# LdcPower.net
KiCad netlist of a schematic drawn in Altium Designer
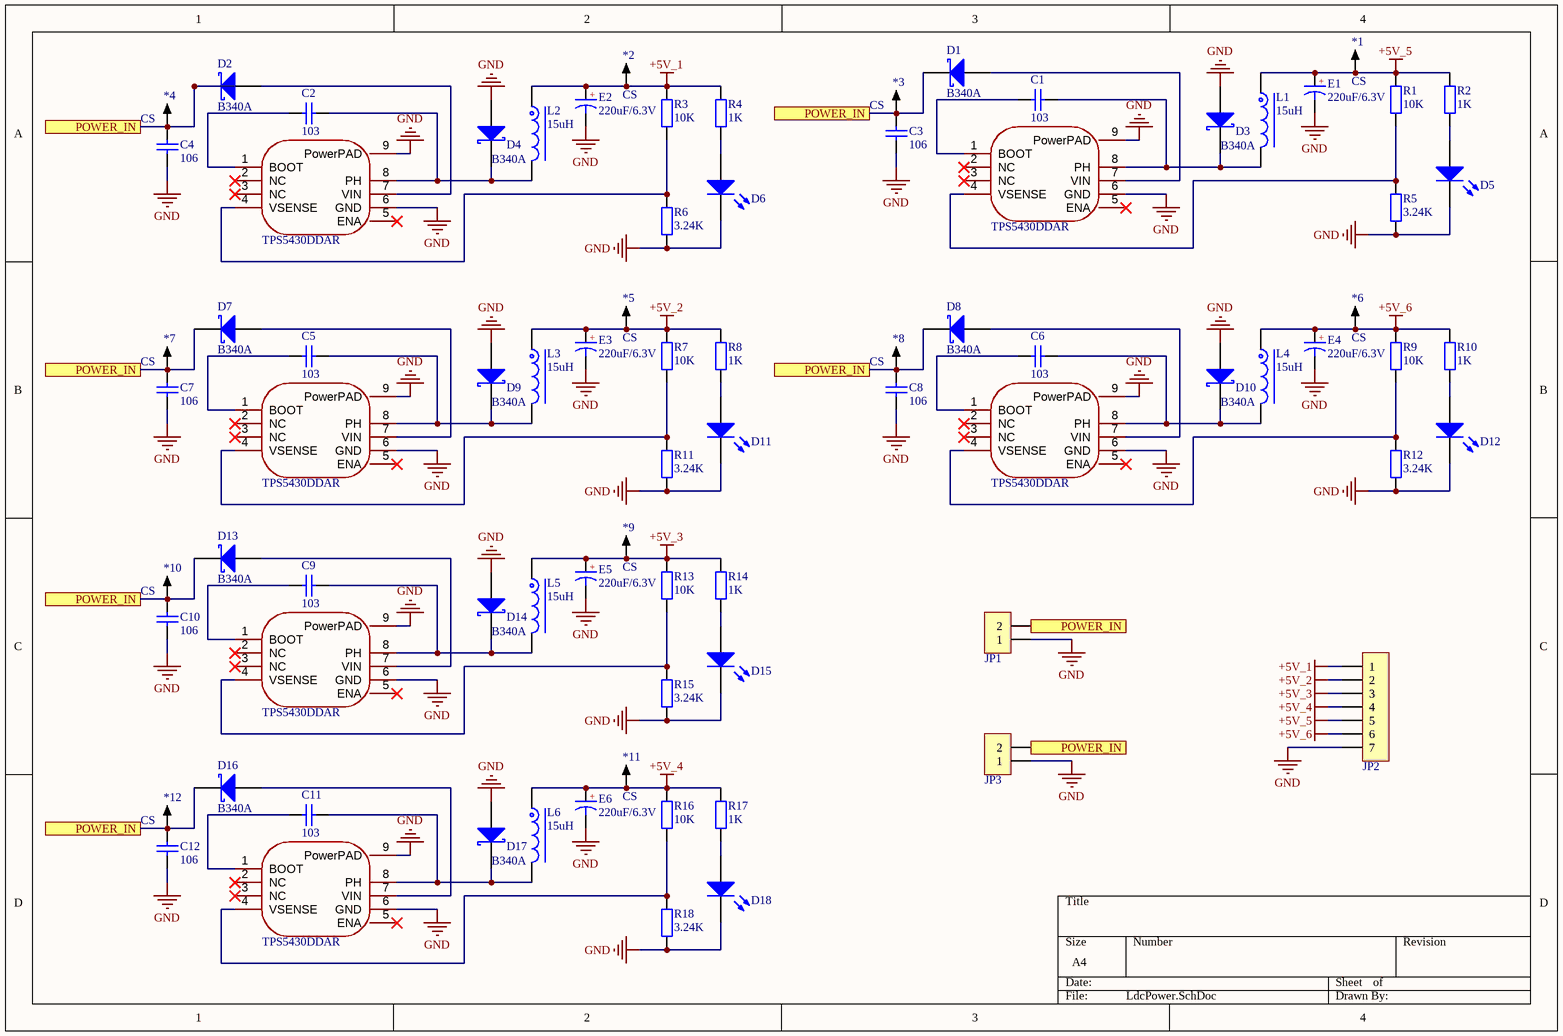
[diagram p0: LdcPower.SchDoc]

(export (version "E")
  (design (tool "Eeschema 10.0.6"))
  (components
    (comp (ref "*1")
      (value "CS")
      (footprint "TEST 1.2")
      (description "探针焊盘")
      (libsource (lib "Wlink") (part "CS"))
    )
    (comp (ref "*2")
      (value "CS")
      (footprint "TEST 1.2")
      (description "探针焊盘")
      (libsource (lib "Wlink") (part "CS"))
    )
    (comp (ref "*3")
      (value "CS")
      (footprint "TEST 1.2")
      (description "探针焊盘")
      (libsource (lib "Wlink") (part "CS"))
    )
    (comp (ref "*4")
      (value "CS")
      (footprint "TEST 1.2")
      (description "探针焊盘")
      (libsource (lib "Wlink") (part "CS"))
    )
    (comp (ref "*5")
      (value "CS")
      (footprint "TEST 1.2")
      (description "探针焊盘")
      (libsource (lib "Wlink") (part "CS"))
    )
    (comp (ref "*6")
      (value "CS")
      (footprint "TEST 1.2")
      (description "探针焊盘")
      (libsource (lib "Wlink") (part "CS"))
    )
    (comp (ref "*7")
      (value "CS")
      (footprint "TEST 1.2")
      (description "探针焊盘")
      (libsource (lib "Wlink") (part "CS"))
    )
    (comp (ref "*8")
      (value "CS")
      (footprint "TEST 1.2")
      (description "探针焊盘")
      (libsource (lib "Wlink") (part "CS"))
    )
    (comp (ref "*9")
      (value "CS")
      (footprint "TEST 1.2")
      (description "探针焊盘")
      (libsource (lib "Wlink") (part "CS"))
    )
    (comp (ref "*10")
      (value "CS")
      (footprint "TEST 1.2")
      (description "探针焊盘")
      (libsource (lib "Wlink") (part "CS"))
    )
    (comp (ref "*11")
      (value "CS")
      (footprint "TEST 1.2")
      (description "探针焊盘")
      (libsource (lib "Wlink") (part "CS"))
    )
    (comp (ref "*12")
      (value "CS")
      (footprint "TEST 1.2")
      (description "探针焊盘")
      (libsource (lib "Wlink") (part "CS"))
    )
    (comp (ref "C1")
      (value "103")
      (footprint "C0603_L")
      (description "贴片电容/MLCC电容")
      (libsource (lib "Wlink") (part "C"))
    )
    (comp (ref "C2")
      (value "103")
      (footprint "C0603_L")
      (description "贴片电容/MLCC电容")
      (libsource (lib "Wlink") (part "C"))
    )
    (comp (ref "C3")
      (value "106")
      (footprint "C0603_L")
      (description "贴片电容/MLCC电容")
      (libsource (lib "Wlink") (part "C"))
    )
    (comp (ref "C4")
      (value "106")
      (footprint "C0603_L")
      (description "贴片电容/MLCC电容")
      (libsource (lib "Wlink") (part "C"))
    )
    (comp (ref "C5")
      (value "103")
      (footprint "C0603_L")
      (description "贴片电容/MLCC电容")
      (libsource (lib "Wlink") (part "C"))
    )
    (comp (ref "C6")
      (value "103")
      (footprint "C0603_L")
      (description "贴片电容/MLCC电容")
      (libsource (lib "Wlink") (part "C"))
    )
    (comp (ref "C7")
      (value "106")
      (footprint "C0603_L")
      (description "贴片电容/MLCC电容")
      (libsource (lib "Wlink") (part "C"))
    )
    (comp (ref "C8")
      (value "106")
      (footprint "C0603_L")
      (description "贴片电容/MLCC电容")
      (libsource (lib "Wlink") (part "C"))
    )
    (comp (ref "C9")
      (value "103")
      (footprint "C0603_L")
      (description "贴片电容/MLCC电容")
      (libsource (lib "Wlink") (part "C"))
    )
    (comp (ref "C10")
      (value "106")
      (footprint "C0603_L")
      (description "贴片电容/MLCC电容")
      (libsource (lib "Wlink") (part "C"))
    )
    (comp (ref "C11")
      (value "103")
      (footprint "C0603_L")
      (description "贴片电容/MLCC电容")
      (libsource (lib "Wlink") (part "C"))
    )
    (comp (ref "C12")
      (value "106")
      (footprint "C0603_L")
      (description "贴片电容/MLCC电容")
      (libsource (lib "Wlink") (part "C"))
    )
    (comp (ref "D1")
      (value "B340A")
      (footprint "SMA")
      (description "肖特基二极管")
      (libsource (lib "Wlink") (part "D-Schottky"))
    )
    (comp (ref "D2")
      (value "B340A")
      (footprint "SMA")
      (description "肖特基二极管")
      (libsource (lib "Wlink") (part "D-Schottky"))
    )
    (comp (ref "D3")
      (value "B340A")
      (footprint "SMA")
      (description "肖特基二极管")
      (libsource (lib "Wlink") (part "D-Schottky"))
    )
    (comp (ref "D4")
      (value "B340A")
      (footprint "SMA")
      (description "肖特基二极管")
      (libsource (lib "Wlink") (part "D-Schottky"))
    )
    (comp (ref "D5")
      (value "LED")
      (footprint "LED0603_R")
      (description "发光二极管")
      (fields (field (name "PUBLISHER") "Altium Limited"))
      (libsource (lib "fszhang") (part "LED0"))
    )
    (comp (ref "D6")
      (value "LED")
      (footprint "LED0603_R")
      (description "发光二极管")
      (fields (field (name "PUBLISHER") "Altium Limited"))
      (libsource (lib "fszhang") (part "LED0"))
    )
    (comp (ref "D7")
      (value "B340A")
      (footprint "SMA")
      (description "肖特基二极管")
      (libsource (lib "Wlink") (part "D-Schottky"))
    )
    (comp (ref "D8")
      (value "B340A")
      (footprint "SMA")
      (description "肖特基二极管")
      (libsource (lib "Wlink") (part "D-Schottky"))
    )
    (comp (ref "D9")
      (value "B340A")
      (footprint "SMA")
      (description "肖特基二极管")
      (libsource (lib "Wlink") (part "D-Schottky"))
    )
    (comp (ref "D10")
      (value "B340A")
      (footprint "SMA")
      (description "肖特基二极管")
      (libsource (lib "Wlink") (part "D-Schottky"))
    )
    (comp (ref "D11")
      (value "LED")
      (footprint "LED0603_R")
      (description "发光二极管")
      (fields (field (name "PUBLISHER") "Altium Limited"))
      (libsource (lib "fszhang") (part "LED0"))
    )
    (comp (ref "D12")
      (value "LED")
      (footprint "LED0603_R")
      (description "发光二极管")
      (fields (field (name "PUBLISHER") "Altium Limited"))
      (libsource (lib "fszhang") (part "LED0"))
    )
    (comp (ref "D13")
      (value "B340A")
      (footprint "SMA")
      (description "肖特基二极管")
      (libsource (lib "Wlink") (part "D-Schottky"))
    )
    (comp (ref "D14")
      (value "B340A")
      (footprint "SMA")
      (description "肖特基二极管")
      (libsource (lib "Wlink") (part "D-Schottky"))
    )
    (comp (ref "D15")
      (value "LED")
      (footprint "LED0603_R")
      (description "发光二极管")
      (fields (field (name "PUBLISHER") "Altium Limited"))
      (libsource (lib "fszhang") (part "LED0"))
    )
    (comp (ref "D16")
      (value "B340A")
      (footprint "SMA")
      (description "肖特基二极管")
      (libsource (lib "Wlink") (part "D-Schottky"))
    )
    (comp (ref "D17")
      (value "B340A")
      (footprint "SMA")
      (description "肖特基二极管")
      (libsource (lib "Wlink") (part "D-Schottky"))
    )
    (comp (ref "D18")
      (value "LED")
      (footprint "LED0603_R")
      (description "发光二极管")
      (fields (field (name "PUBLISHER") "Altium Limited"))
      (libsource (lib "fszhang") (part "LED0"))
    )
    (comp (ref "E1")
      (value "220uF/6.3V")
      (footprint "C_3528")
      (description "贴片钽电容")
      (libsource (lib "Wlink") (part "CT"))
    )
    (comp (ref "E2")
      (value "220uF/6.3V")
      (footprint "C_3528")
      (description "贴片钽电容")
      (libsource (lib "Wlink") (part "CT"))
    )
    (comp (ref "E3")
      (value "220uF/6.3V")
      (footprint "C_3528")
      (description "贴片钽电容")
      (libsource (lib "Wlink") (part "CT"))
    )
    (comp (ref "E4")
      (value "220uF/6.3V")
      (footprint "C_3528")
      (description "贴片钽电容")
      (libsource (lib "Wlink") (part "CT"))
    )
    (comp (ref "E5")
      (value "220uF/6.3V")
      (footprint "C_3528")
      (description "贴片钽电容")
      (libsource (lib "Wlink") (part "CT"))
    )
    (comp (ref "E6")
      (value "220uF/6.3V")
      (footprint "C_3528")
      (description "贴片钽电容")
      (libsource (lib "Wlink") (part "CT"))
    )
    (comp (ref "JP1")
      (value "HDR-1X2")
      (footprint "CONN-TH_XT60PW-M")
      (description "2P接插件")
      (libsource (lib "5.5 - 2.54mm连接器(KF2EDGK_XH2.54_2.54排针排母)") (part "Header 2"))
    )
    (comp (ref "JP2")
      (value "HDR-1X7")
      (footprint "CONN-SMD_7P-P2.54_MEGASTAR_ZX-XH2.54-7PWT")
      (description "7P接插件")
      (libsource (lib "MultiChannelLdc") (part "Header 7"))
    )
    (comp (ref "JP3")
      (value "HDR-1X2")
      (footprint "CONN-SMD_2P-P2.54_MEGASTAR_ZX-XH2.54-2PWT")
      (description "2P接插件")
      (libsource (lib "5.5 - 2.54mm连接器(KF2EDGK_XH2.54_2.54排针排母)") (part "Header 2"))
    )
    (comp (ref "L1")
      (value "15uH")
      (footprint "L-SMD-0630")
      (description "一体成型电感")
      (libsource (lib "Wlink") (part "L-Molding Choke"))
    )
    (comp (ref "L2")
      (value "15uH")
      (footprint "L-SMD-0630")
      (description "一体成型电感")
      (libsource (lib "Wlink") (part "L-Molding Choke"))
    )
    (comp (ref "L3")
      (value "15uH")
      (footprint "L-SMD-0630")
      (description "一体成型电感")
      (libsource (lib "Wlink") (part "L-Molding Choke"))
    )
    (comp (ref "L4")
      (value "15uH")
      (footprint "L-SMD-0630")
      (description "一体成型电感")
      (libsource (lib "Wlink") (part "L-Molding Choke"))
    )
    (comp (ref "L5")
      (value "15uH")
      (footprint "L-SMD-0630")
      (description "一体成型电感")
      (libsource (lib "Wlink") (part "L-Molding Choke"))
    )
    (comp (ref "L6")
      (value "15uH")
      (footprint "L-SMD-0630")
      (description "一体成型电感")
      (libsource (lib "Wlink") (part "L-Molding Choke"))
    )
    (comp (ref "R1")
      (value "10K")
      (footprint "R0603_L")
      (description "贴片电阻")
      (libsource (lib "Wlink") (part "R"))
    )
    (comp (ref "R2")
      (value "1K")
      (footprint "R0603_L")
      (description "贴片电阻")
      (libsource (lib "Wlink") (part "R"))
    )
    (comp (ref "R3")
      (value "10K")
      (footprint "R0603_L")
      (description "贴片电阻")
      (libsource (lib "Wlink") (part "R"))
    )
    (comp (ref "R4")
      (value "1K")
      (footprint "R0603_L")
      (description "贴片电阻")
      (libsource (lib "Wlink") (part "R"))
    )
    (comp (ref "R5")
      (value "3.24K")
      (footprint "R0603_L")
      (description "贴片电阻")
      (libsource (lib "Wlink") (part "R"))
    )
    (comp (ref "R6")
      (value "3.24K")
      (footprint "R0603_L")
      (description "贴片电阻")
      (libsource (lib "Wlink") (part "R"))
    )
    (comp (ref "R7")
      (value "10K")
      (footprint "R0603_L")
      (description "贴片电阻")
      (libsource (lib "Wlink") (part "R"))
    )
    (comp (ref "R8")
      (value "1K")
      (footprint "R0603_L")
      (description "贴片电阻")
      (libsource (lib "Wlink") (part "R"))
    )
    (comp (ref "R9")
      (value "10K")
      (footprint "R0603_L")
      (description "贴片电阻")
      (libsource (lib "Wlink") (part "R"))
    )
    (comp (ref "R10")
      (value "1K")
      (footprint "R0603_L")
      (description "贴片电阻")
      (libsource (lib "Wlink") (part "R"))
    )
    (comp (ref "R11")
      (value "3.24K")
      (footprint "R0603_L")
      (description "贴片电阻")
      (libsource (lib "Wlink") (part "R"))
    )
    (comp (ref "R12")
      (value "3.24K")
      (footprint "R0603_L")
      (description "贴片电阻")
      (libsource (lib "Wlink") (part "R"))
    )
    (comp (ref "R13")
      (value "10K")
      (footprint "R0603_L")
      (description "贴片电阻")
      (libsource (lib "Wlink") (part "R"))
    )
    (comp (ref "R14")
      (value "1K")
      (footprint "R0603_L")
      (description "贴片电阻")
      (libsource (lib "Wlink") (part "R"))
    )
    (comp (ref "R15")
      (value "3.24K")
      (footprint "R0603_L")
      (description "贴片电阻")
      (libsource (lib "Wlink") (part "R"))
    )
    (comp (ref "R16")
      (value "10K")
      (footprint "R0603_L")
      (description "贴片电阻")
      (libsource (lib "Wlink") (part "R"))
    )
    (comp (ref "R17")
      (value "1K")
      (footprint "R0603_L")
      (description "贴片电阻")
      (libsource (lib "Wlink") (part "R"))
    )
    (comp (ref "R18")
      (value "3.24K")
      (footprint "R0603_L")
      (description "贴片电阻")
      (libsource (lib "Wlink") (part "R"))
    )
    (comp (ref "U1")
      (value "TPS5430DDAR")
      (footprint "SOIC-8_EP")
      (libsource (lib "Wlink") (part "TPS5430DDAR"))
    )
    (comp (ref "U2")
      (value "TPS5430DDAR")
      (footprint "SOIC-8_EP")
      (libsource (lib "Wlink") (part "TPS5430DDAR"))
    )
    (comp (ref "U3")
      (value "TPS5430DDAR")
      (footprint "SOIC-8_EP")
      (libsource (lib "Wlink") (part "TPS5430DDAR"))
    )
    (comp (ref "U4")
      (value "TPS5430DDAR")
      (footprint "SOIC-8_EP")
      (libsource (lib "Wlink") (part "TPS5430DDAR"))
    )
    (comp (ref "U5")
      (value "TPS5430DDAR")
      (footprint "SOIC-8_EP")
      (libsource (lib "Wlink") (part "TPS5430DDAR"))
    )
    (comp (ref "U6")
      (value "TPS5430DDAR")
      (footprint "SOIC-8_EP")
      (libsource (lib "Wlink") (part "TPS5430DDAR"))
    )
  )
  (nets
    (net (code "1") (name "+5V_1") (class "Default")
      (node (ref "*2") (pin "1") (pinfunction "1_1") (pintype "passive"))
      (node (ref "E2") (pin "1") (pinfunction "A_1") (pintype "passive"))
      (node (ref "JP2") (pin "1") (pinfunction "1_1") (pintype "passive"))
      (node (ref "L2") (pin "1") (pinfunction "1_1") (pintype "passive"))
      (node (ref "R3") (pin "2") (pinfunction "2_2") (pintype "passive"))
      (node (ref "R4") (pin "2") (pinfunction "2_2") (pintype "passive"))
    )
    (net (code "2") (name "+5V_2") (class "Default")
      (node (ref "*5") (pin "1") (pinfunction "1_1") (pintype "passive"))
      (node (ref "E3") (pin "1") (pinfunction "A_1") (pintype "passive"))
      (node (ref "JP2") (pin "2") (pinfunction "2_2") (pintype "passive"))
      (node (ref "L3") (pin "1") (pinfunction "1_1") (pintype "passive"))
      (node (ref "R7") (pin "2") (pinfunction "2_2") (pintype "passive"))
      (node (ref "R8") (pin "2") (pinfunction "2_2") (pintype "passive"))
    )
    (net (code "3") (name "+5V_3") (class "Default")
      (node (ref "*9") (pin "1") (pinfunction "1_1") (pintype "passive"))
      (node (ref "E5") (pin "1") (pinfunction "A_1") (pintype "passive"))
      (node (ref "JP2") (pin "3") (pinfunction "3_3") (pintype "passive"))
      (node (ref "L5") (pin "1") (pinfunction "1_1") (pintype "passive"))
      (node (ref "R13") (pin "2") (pinfunction "2_2") (pintype "passive"))
      (node (ref "R14") (pin "2") (pinfunction "2_2") (pintype "passive"))
    )
    (net (code "4") (name "+5V_4") (class "Default")
      (node (ref "*11") (pin "1") (pinfunction "1_1") (pintype "passive"))
      (node (ref "E6") (pin "1") (pinfunction "A_1") (pintype "passive"))
      (node (ref "JP2") (pin "4") (pinfunction "4_4") (pintype "passive"))
      (node (ref "L6") (pin "1") (pinfunction "1_1") (pintype "passive"))
      (node (ref "R16") (pin "2") (pinfunction "2_2") (pintype "passive"))
      (node (ref "R17") (pin "2") (pinfunction "2_2") (pintype "passive"))
    )
    (net (code "5") (name "+5V_5") (class "Default")
      (node (ref "*1") (pin "1") (pinfunction "1_1") (pintype "passive"))
      (node (ref "E1") (pin "1") (pinfunction "A_1") (pintype "passive"))
      (node (ref "JP2") (pin "5") (pinfunction "5_5") (pintype "passive"))
      (node (ref "L1") (pin "1") (pinfunction "1_1") (pintype "passive"))
      (node (ref "R1") (pin "2") (pinfunction "2_2") (pintype "passive"))
      (node (ref "R2") (pin "2") (pinfunction "2_2") (pintype "passive"))
    )
    (net (code "6") (name "+5V_6") (class "Default")
      (node (ref "*6") (pin "1") (pinfunction "1_1") (pintype "passive"))
      (node (ref "E4") (pin "1") (pinfunction "A_1") (pintype "passive"))
      (node (ref "JP2") (pin "6") (pinfunction "6_6") (pintype "passive"))
      (node (ref "L4") (pin "1") (pinfunction "1_1") (pintype "passive"))
      (node (ref "R10") (pin "2") (pinfunction "2_2") (pintype "passive"))
      (node (ref "R9") (pin "2") (pinfunction "2_2") (pintype "passive"))
    )
    (net (code "7") (name "/POWER_IN") (class "Default")
      (node (ref "*10") (pin "1") (pinfunction "1_1") (pintype "passive"))
      (node (ref "*12") (pin "1") (pinfunction "1_1") (pintype "passive"))
      (node (ref "*3") (pin "1") (pinfunction "1_1") (pintype "passive"))
      (node (ref "*4") (pin "1") (pinfunction "1_1") (pintype "passive"))
      (node (ref "*7") (pin "1") (pinfunction "1_1") (pintype "passive"))
      (node (ref "*8") (pin "1") (pinfunction "1_1") (pintype "passive"))
      (node (ref "C10") (pin "2") (pinfunction "2_2") (pintype "passive"))
      (node (ref "C12") (pin "2") (pinfunction "2_2") (pintype "passive"))
      (node (ref "C3") (pin "2") (pinfunction "2_2") (pintype "passive"))
      (node (ref "C4") (pin "2") (pinfunction "2_2") (pintype "passive"))
      (node (ref "C7") (pin "2") (pinfunction "2_2") (pintype "passive"))
      (node (ref "C8") (pin "2") (pinfunction "2_2") (pintype "passive"))
      (node (ref "D1") (pin "2") (pinfunction "K_2") (pintype "passive"))
      (node (ref "D13") (pin "2") (pinfunction "K_2") (pintype "passive"))
      (node (ref "D16") (pin "2") (pinfunction "K_2") (pintype "passive"))
      (node (ref "D2") (pin "2") (pinfunction "K_2") (pintype "passive"))
      (node (ref "D7") (pin "2") (pinfunction "K_2") (pintype "passive"))
      (node (ref "D8") (pin "2") (pinfunction "K_2") (pintype "passive"))
      (node (ref "JP1") (pin "2") (pinfunction "2_2") (pintype "passive"))
      (node (ref "JP3") (pin "2") (pinfunction "2_2") (pintype "passive"))
    )
    (net (code "8") (name "GND") (class "Default")
      (node (ref "C10") (pin "1") (pinfunction "1_1") (pintype "passive"))
      (node (ref "C12") (pin "1") (pinfunction "1_1") (pintype "passive"))
      (node (ref "C3") (pin "1") (pinfunction "1_1") (pintype "passive"))
      (node (ref "C4") (pin "1") (pinfunction "1_1") (pintype "passive"))
      (node (ref "C7") (pin "1") (pinfunction "1_1") (pintype "passive"))
      (node (ref "C8") (pin "1") (pinfunction "1_1") (pintype "passive"))
      (node (ref "D10") (pin "1") (pinfunction "A_1") (pintype "passive"))
      (node (ref "D11") (pin "2") (pinfunction "K_2") (pintype "passive"))
      (node (ref "D12") (pin "2") (pinfunction "K_2") (pintype "passive"))
      (node (ref "D14") (pin "1") (pinfunction "A_1") (pintype "passive"))
      (node (ref "D15") (pin "2") (pinfunction "K_2") (pintype "passive"))
      (node (ref "D17") (pin "1") (pinfunction "A_1") (pintype "passive"))
      (node (ref "D18") (pin "2") (pinfunction "K_2") (pintype "passive"))
      (node (ref "D3") (pin "1") (pinfunction "A_1") (pintype "passive"))
      (node (ref "D4") (pin "1") (pinfunction "A_1") (pintype "passive"))
      (node (ref "D5") (pin "2") (pinfunction "K_2") (pintype "passive"))
      (node (ref "D6") (pin "2") (pinfunction "K_2") (pintype "passive"))
      (node (ref "D9") (pin "1") (pinfunction "A_1") (pintype "passive"))
      (node (ref "E1") (pin "2") (pinfunction "K_2") (pintype "passive"))
      (node (ref "E2") (pin "2") (pinfunction "K_2") (pintype "passive"))
      (node (ref "E3") (pin "2") (pinfunction "K_2") (pintype "passive"))
      (node (ref "E4") (pin "2") (pinfunction "K_2") (pintype "passive"))
      (node (ref "E5") (pin "2") (pinfunction "K_2") (pintype "passive"))
      (node (ref "E6") (pin "2") (pinfunction "K_2") (pintype "passive"))
      (node (ref "JP1") (pin "1") (pinfunction "1_1") (pintype "passive"))
      (node (ref "JP2") (pin "7") (pinfunction "7_7") (pintype "passive"))
      (node (ref "JP3") (pin "1") (pinfunction "1_1") (pintype "passive"))
      (node (ref "R11") (pin "1") (pinfunction "1_1") (pintype "passive"))
      (node (ref "R12") (pin "1") (pinfunction "1_1") (pintype "passive"))
      (node (ref "R15") (pin "1") (pinfunction "1_1") (pintype "passive"))
      (node (ref "R18") (pin "1") (pinfunction "1_1") (pintype "passive"))
      (node (ref "R5") (pin "1") (pinfunction "1_1") (pintype "passive"))
      (node (ref "R6") (pin "1") (pinfunction "1_1") (pintype "passive"))
      (node (ref "U1") (pin "6") (pinfunction "GND_6") (pintype "passive"))
      (node (ref "U1") (pin "9") (pinfunction "PowerPAD_9") (pintype "passive"))
      (node (ref "U2") (pin "6") (pinfunction "GND_6") (pintype "passive"))
      (node (ref "U2") (pin "9") (pinfunction "PowerPAD_9") (pintype "passive"))
      (node (ref "U3") (pin "6") (pinfunction "GND_6") (pintype "passive"))
      (node (ref "U3") (pin "9") (pinfunction "PowerPAD_9") (pintype "passive"))
      (node (ref "U4") (pin "6") (pinfunction "GND_6") (pintype "passive"))
      (node (ref "U4") (pin "9") (pinfunction "PowerPAD_9") (pintype "passive"))
      (node (ref "U5") (pin "6") (pinfunction "GND_6") (pintype "passive"))
      (node (ref "U5") (pin "9") (pinfunction "PowerPAD_9") (pintype "passive"))
      (node (ref "U6") (pin "6") (pinfunction "GND_6") (pintype "passive"))
      (node (ref "U6") (pin "9") (pinfunction "PowerPAD_9") (pintype "passive"))
    )
    (net (code "9") (name "Net-(D1-A)") (class "Default")
      (node (ref "D1") (pin "1") (pinfunction "A_1") (pintype "passive"))
      (node (ref "U1") (pin "7") (pinfunction "VIN_7") (pintype "passive"))
    )
    (net (code "10") (name "Net-(D2-A)") (class "Default")
      (node (ref "D2") (pin "1") (pinfunction "A_1") (pintype "passive"))
      (node (ref "U2") (pin "7") (pinfunction "VIN_7") (pintype "passive"))
    )
    (net (code "11") (name "Net-(D3-K)") (class "Default")
      (node (ref "C1") (pin "2") (pinfunction "2_2") (pintype "passive"))
      (node (ref "D3") (pin "2") (pinfunction "K_2") (pintype "passive"))
      (node (ref "L1") (pin "2") (pinfunction "2_2") (pintype "passive"))
      (node (ref "U1") (pin "8") (pinfunction "PH_8") (pintype "passive"))
    )
    (net (code "12") (name "Net-(D4-K)") (class "Default")
      (node (ref "C2") (pin "2") (pinfunction "2_2") (pintype "passive"))
      (node (ref "D4") (pin "2") (pinfunction "K_2") (pintype "passive"))
      (node (ref "L2") (pin "2") (pinfunction "2_2") (pintype "passive"))
      (node (ref "U2") (pin "8") (pinfunction "PH_8") (pintype "passive"))
    )
    (net (code "13") (name "Net-(D5-A)") (class "Default")
      (node (ref "D5") (pin "1") (pinfunction "A_1") (pintype "passive"))
      (node (ref "R2") (pin "1") (pinfunction "1_1") (pintype "passive"))
    )
    (net (code "14") (name "Net-(D6-A)") (class "Default")
      (node (ref "D6") (pin "1") (pinfunction "A_1") (pintype "passive"))
      (node (ref "R4") (pin "1") (pinfunction "1_1") (pintype "passive"))
    )
    (net (code "15") (name "Net-(D7-A)") (class "Default")
      (node (ref "D7") (pin "1") (pinfunction "A_1") (pintype "passive"))
      (node (ref "U3") (pin "7") (pinfunction "VIN_7") (pintype "passive"))
    )
    (net (code "16") (name "Net-(D8-A)") (class "Default")
      (node (ref "D8") (pin "1") (pinfunction "A_1") (pintype "passive"))
      (node (ref "U4") (pin "7") (pinfunction "VIN_7") (pintype "passive"))
    )
    (net (code "17") (name "Net-(D9-K)") (class "Default")
      (node (ref "C5") (pin "2") (pinfunction "2_2") (pintype "passive"))
      (node (ref "D9") (pin "2") (pinfunction "K_2") (pintype "passive"))
      (node (ref "L3") (pin "2") (pinfunction "2_2") (pintype "passive"))
      (node (ref "U3") (pin "8") (pinfunction "PH_8") (pintype "passive"))
    )
    (net (code "18") (name "Net-(D10-K)") (class "Default")
      (node (ref "C6") (pin "2") (pinfunction "2_2") (pintype "passive"))
      (node (ref "D10") (pin "2") (pinfunction "K_2") (pintype "passive"))
      (node (ref "L4") (pin "2") (pinfunction "2_2") (pintype "passive"))
      (node (ref "U4") (pin "8") (pinfunction "PH_8") (pintype "passive"))
    )
    (net (code "19") (name "Net-(D11-A)") (class "Default")
      (node (ref "D11") (pin "1") (pinfunction "A_1") (pintype "passive"))
      (node (ref "R8") (pin "1") (pinfunction "1_1") (pintype "passive"))
    )
    (net (code "20") (name "Net-(D12-A)") (class "Default")
      (node (ref "D12") (pin "1") (pinfunction "A_1") (pintype "passive"))
      (node (ref "R10") (pin "1") (pinfunction "1_1") (pintype "passive"))
    )
    (net (code "21") (name "Net-(D13-A)") (class "Default")
      (node (ref "D13") (pin "1") (pinfunction "A_1") (pintype "passive"))
      (node (ref "U5") (pin "7") (pinfunction "VIN_7") (pintype "passive"))
    )
    (net (code "22") (name "Net-(D14-K)") (class "Default")
      (node (ref "C9") (pin "2") (pinfunction "2_2") (pintype "passive"))
      (node (ref "D14") (pin "2") (pinfunction "K_2") (pintype "passive"))
      (node (ref "L5") (pin "2") (pinfunction "2_2") (pintype "passive"))
      (node (ref "U5") (pin "8") (pinfunction "PH_8") (pintype "passive"))
    )
    (net (code "23") (name "Net-(D15-A)") (class "Default")
      (node (ref "D15") (pin "1") (pinfunction "A_1") (pintype "passive"))
      (node (ref "R14") (pin "1") (pinfunction "1_1") (pintype "passive"))
    )
    (net (code "24") (name "Net-(D16-A)") (class "Default")
      (node (ref "D16") (pin "1") (pinfunction "A_1") (pintype "passive"))
      (node (ref "U6") (pin "7") (pinfunction "VIN_7") (pintype "passive"))
    )
    (net (code "25") (name "Net-(D17-K)") (class "Default")
      (node (ref "C11") (pin "2") (pinfunction "2_2") (pintype "passive"))
      (node (ref "D17") (pin "2") (pinfunction "K_2") (pintype "passive"))
      (node (ref "L6") (pin "2") (pinfunction "2_2") (pintype "passive"))
      (node (ref "U6") (pin "8") (pinfunction "PH_8") (pintype "passive"))
    )
    (net (code "26") (name "Net-(D18-A)") (class "Default")
      (node (ref "D18") (pin "1") (pinfunction "A_1") (pintype "passive"))
      (node (ref "R17") (pin "1") (pinfunction "1_1") (pintype "passive"))
    )
    (net (code "27") (name "Net-(U1-BOOT)") (class "Default")
      (node (ref "C1") (pin "1") (pinfunction "1_1") (pintype "passive"))
      (node (ref "U1") (pin "1") (pinfunction "BOOT_1") (pintype "passive"))
    )
    (net (code "28") (name "Net-(U1-VSENSE)") (class "Default")
      (node (ref "R1") (pin "1") (pinfunction "1_1") (pintype "passive"))
      (node (ref "R5") (pin "2") (pinfunction "2_2") (pintype "passive"))
      (node (ref "U1") (pin "4") (pinfunction "VSENSE_4") (pintype "passive"))
    )
    (net (code "29") (name "Net-(U2-BOOT)") (class "Default")
      (node (ref "C2") (pin "1") (pinfunction "1_1") (pintype "passive"))
      (node (ref "U2") (pin "1") (pinfunction "BOOT_1") (pintype "passive"))
    )
    (net (code "30") (name "Net-(U2-VSENSE)") (class "Default")
      (node (ref "R3") (pin "1") (pinfunction "1_1") (pintype "passive"))
      (node (ref "R6") (pin "2") (pinfunction "2_2") (pintype "passive"))
      (node (ref "U2") (pin "4") (pinfunction "VSENSE_4") (pintype "passive"))
    )
    (net (code "31") (name "Net-(U3-BOOT)") (class "Default")
      (node (ref "C5") (pin "1") (pinfunction "1_1") (pintype "passive"))
      (node (ref "U3") (pin "1") (pinfunction "BOOT_1") (pintype "passive"))
    )
    (net (code "32") (name "Net-(U3-VSENSE)") (class "Default")
      (node (ref "R11") (pin "2") (pinfunction "2_2") (pintype "passive"))
      (node (ref "R7") (pin "1") (pinfunction "1_1") (pintype "passive"))
      (node (ref "U3") (pin "4") (pinfunction "VSENSE_4") (pintype "passive"))
    )
    (net (code "33") (name "Net-(U4-BOOT)") (class "Default")
      (node (ref "C6") (pin "1") (pinfunction "1_1") (pintype "passive"))
      (node (ref "U4") (pin "1") (pinfunction "BOOT_1") (pintype "passive"))
    )
    (net (code "34") (name "Net-(U4-VSENSE)") (class "Default")
      (node (ref "R12") (pin "2") (pinfunction "2_2") (pintype "passive"))
      (node (ref "R9") (pin "1") (pinfunction "1_1") (pintype "passive"))
      (node (ref "U4") (pin "4") (pinfunction "VSENSE_4") (pintype "passive"))
    )
    (net (code "35") (name "Net-(U5-BOOT)") (class "Default")
      (node (ref "C9") (pin "1") (pinfunction "1_1") (pintype "passive"))
      (node (ref "U5") (pin "1") (pinfunction "BOOT_1") (pintype "passive"))
    )
    (net (code "36") (name "Net-(U5-VSENSE)") (class "Default")
      (node (ref "R13") (pin "1") (pinfunction "1_1") (pintype "passive"))
      (node (ref "R15") (pin "2") (pinfunction "2_2") (pintype "passive"))
      (node (ref "U5") (pin "4") (pinfunction "VSENSE_4") (pintype "passive"))
    )
    (net (code "37") (name "Net-(U6-BOOT)") (class "Default")
      (node (ref "C11") (pin "1") (pinfunction "1_1") (pintype "passive"))
      (node (ref "U6") (pin "1") (pinfunction "BOOT_1") (pintype "passive"))
    )
    (net (code "38") (name "Net-(U6-VSENSE)") (class "Default")
      (node (ref "R16") (pin "1") (pinfunction "1_1") (pintype "passive"))
      (node (ref "R18") (pin "2") (pinfunction "2_2") (pintype "passive"))
      (node (ref "U6") (pin "4") (pinfunction "VSENSE_4") (pintype "passive"))
    )
    (net (code "39") (name "unconnected-(U1-ENA-Pad5)") (class "Default")
      (node (ref "U1") (pin "5") (pinfunction "ENA_5") (pintype "passive+no_connect"))
    )
    (net (code "40") (name "unconnected-(U1-NC-Pad2)") (class "Default")
      (node (ref "U1") (pin "2") (pinfunction "NC_2") (pintype "passive+no_connect"))
    )
    (net (code "41") (name "unconnected-(U1-NC-Pad3)") (class "Default")
      (node (ref "U1") (pin "3") (pinfunction "NC_3") (pintype "passive+no_connect"))
    )
    (net (code "42") (name "unconnected-(U2-ENA-Pad5)") (class "Default")
      (node (ref "U2") (pin "5") (pinfunction "ENA_5") (pintype "passive+no_connect"))
    )
    (net (code "43") (name "unconnected-(U2-NC-Pad2)") (class "Default")
      (node (ref "U2") (pin "2") (pinfunction "NC_2") (pintype "passive+no_connect"))
    )
    (net (code "44") (name "unconnected-(U2-NC-Pad3)") (class "Default")
      (node (ref "U2") (pin "3") (pinfunction "NC_3") (pintype "passive+no_connect"))
    )
    (net (code "45") (name "unconnected-(U3-ENA-Pad5)") (class "Default")
      (node (ref "U3") (pin "5") (pinfunction "ENA_5") (pintype "passive+no_connect"))
    )
    (net (code "46") (name "unconnected-(U3-NC-Pad2)") (class "Default")
      (node (ref "U3") (pin "2") (pinfunction "NC_2") (pintype "passive+no_connect"))
    )
    (net (code "47") (name "unconnected-(U3-NC-Pad3)") (class "Default")
      (node (ref "U3") (pin "3") (pinfunction "NC_3") (pintype "passive+no_connect"))
    )
    (net (code "48") (name "unconnected-(U4-ENA-Pad5)") (class "Default")
      (node (ref "U4") (pin "5") (pinfunction "ENA_5") (pintype "passive+no_connect"))
    )
    (net (code "49") (name "unconnected-(U4-NC-Pad2)") (class "Default")
      (node (ref "U4") (pin "2") (pinfunction "NC_2") (pintype "passive+no_connect"))
    )
    (net (code "50") (name "unconnected-(U4-NC-Pad3)") (class "Default")
      (node (ref "U4") (pin "3") (pinfunction "NC_3") (pintype "passive+no_connect"))
    )
    (net (code "51") (name "unconnected-(U5-ENA-Pad5)") (class "Default")
      (node (ref "U5") (pin "5") (pinfunction "ENA_5") (pintype "passive+no_connect"))
    )
    (net (code "52") (name "unconnected-(U5-NC-Pad2)") (class "Default")
      (node (ref "U5") (pin "2") (pinfunction "NC_2") (pintype "passive+no_connect"))
    )
    (net (code "53") (name "unconnected-(U5-NC-Pad3)") (class "Default")
      (node (ref "U5") (pin "3") (pinfunction "NC_3") (pintype "passive+no_connect"))
    )
    (net (code "54") (name "unconnected-(U6-ENA-Pad5)") (class "Default")
      (node (ref "U6") (pin "5") (pinfunction "ENA_5") (pintype "passive+no_connect"))
    )
    (net (code "55") (name "unconnected-(U6-NC-Pad2)") (class "Default")
      (node (ref "U6") (pin "2") (pinfunction "NC_2") (pintype "passive+no_connect"))
    )
    (net (code "56") (name "unconnected-(U6-NC-Pad3)") (class "Default")
      (node (ref "U6") (pin "3") (pinfunction "NC_3") (pintype "passive+no_connect"))
    )
  )
)
